# Sheet1.net
KiCad netlist of a schematic drawn in Altium Designer
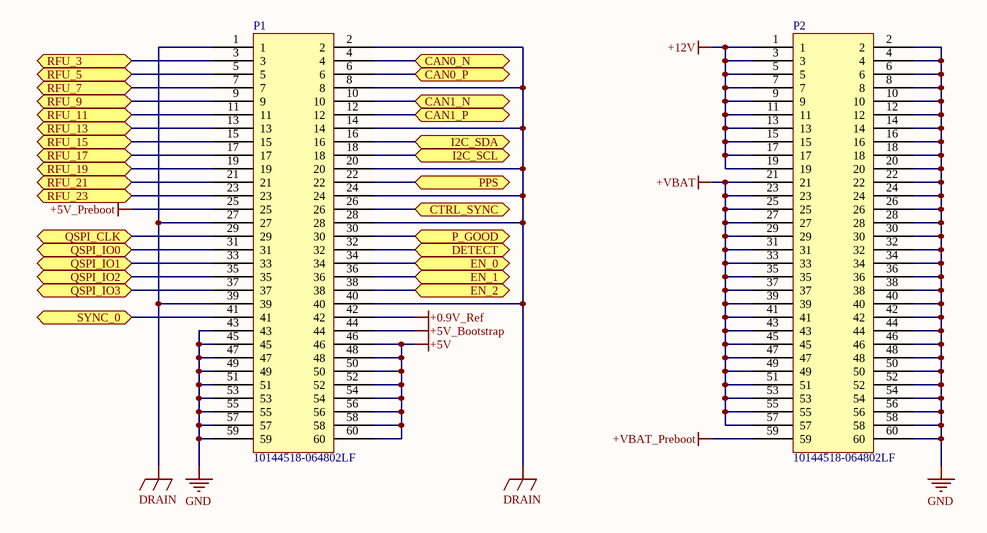
[diagram p0: Sheet1.SchDoc]

(export (version "E")
  (design (tool "Eeschema 10.0.6"))
  (components
    (comp (ref "P1")
      (value "10144518-064802LF")
      (footprint "10144518-064802LF")
      (libsource (lib "ModularPayload") (part "10144518-064802LF"))
    )
    (comp (ref "P2")
      (value "10144518-064802LF")
      (footprint "10144518-064802LF")
      (libsource (lib "ModularPayload") (part "10144518-064802LF"))
    )
  )
  (nets
    (net (code "1") (name "+0.9V_Ref") (class "Default")
      (node (ref "P1") (pin "42") (pinfunction "42_42") (pintype "passive"))
    )
    (net (code "2") (name "+5V") (class "Default")
      (node (ref "P1") (pin "46") (pinfunction "46_46") (pintype "passive"))
      (node (ref "P1") (pin "48") (pinfunction "48_48") (pintype "passive"))
      (node (ref "P1") (pin "50") (pinfunction "50_50") (pintype "passive"))
      (node (ref "P1") (pin "52") (pinfunction "52_52") (pintype "passive"))
      (node (ref "P1") (pin "54") (pinfunction "54_54") (pintype "passive"))
      (node (ref "P1") (pin "56") (pinfunction "56_56") (pintype "passive"))
      (node (ref "P1") (pin "58") (pinfunction "58_58") (pintype "passive"))
      (node (ref "P1") (pin "60") (pinfunction "60_60") (pintype "passive"))
    )
    (net (code "3") (name "+5V_Bootstrap") (class "Default")
      (node (ref "P1") (pin "44") (pinfunction "44_44") (pintype "passive"))
    )
    (net (code "4") (name "+5V_Preboot") (class "Default")
      (node (ref "P1") (pin "25") (pinfunction "25_25") (pintype "passive"))
    )
    (net (code "5") (name "+12V") (class "Default")
      (node (ref "P2") (pin "1") (pinfunction "1_1") (pintype "passive"))
      (node (ref "P2") (pin "11") (pinfunction "11_11") (pintype "passive"))
      (node (ref "P2") (pin "13") (pinfunction "13_13") (pintype "passive"))
      (node (ref "P2") (pin "15") (pinfunction "15_15") (pintype "passive"))
      (node (ref "P2") (pin "17") (pinfunction "17_17") (pintype "passive"))
      (node (ref "P2") (pin "19") (pinfunction "19_19") (pintype "passive"))
      (node (ref "P2") (pin "3") (pinfunction "3_3") (pintype "passive"))
      (node (ref "P2") (pin "5") (pinfunction "5_5") (pintype "passive"))
      (node (ref "P2") (pin "7") (pinfunction "7_7") (pintype "passive"))
      (node (ref "P2") (pin "9") (pinfunction "9_9") (pintype "passive"))
    )
    (net (code "6") (name "+VBAT") (class "Default")
      (node (ref "P2") (pin "21") (pinfunction "21_21") (pintype "passive"))
      (node (ref "P2") (pin "23") (pinfunction "23_23") (pintype "passive"))
      (node (ref "P2") (pin "25") (pinfunction "25_25") (pintype "passive"))
      (node (ref "P2") (pin "27") (pinfunction "27_27") (pintype "passive"))
      (node (ref "P2") (pin "29") (pinfunction "29_29") (pintype "passive"))
      (node (ref "P2") (pin "31") (pinfunction "31_31") (pintype "passive"))
      (node (ref "P2") (pin "33") (pinfunction "33_33") (pintype "passive"))
      (node (ref "P2") (pin "35") (pinfunction "35_35") (pintype "passive"))
      (node (ref "P2") (pin "37") (pinfunction "37_37") (pintype "passive"))
      (node (ref "P2") (pin "39") (pinfunction "39_39") (pintype "passive"))
      (node (ref "P2") (pin "41") (pinfunction "41_41") (pintype "passive"))
      (node (ref "P2") (pin "43") (pinfunction "43_43") (pintype "passive"))
      (node (ref "P2") (pin "45") (pinfunction "45_45") (pintype "passive"))
      (node (ref "P2") (pin "47") (pinfunction "47_47") (pintype "passive"))
      (node (ref "P2") (pin "49") (pinfunction "49_49") (pintype "passive"))
      (node (ref "P2") (pin "51") (pinfunction "51_51") (pintype "passive"))
      (node (ref "P2") (pin "53") (pinfunction "53_53") (pintype "passive"))
      (node (ref "P2") (pin "55") (pinfunction "55_55") (pintype "passive"))
      (node (ref "P2") (pin "57") (pinfunction "57_57") (pintype "passive"))
    )
    (net (code "7") (name "+VBAT_Preboot") (class "Default")
      (node (ref "P2") (pin "59") (pinfunction "59_59") (pintype "passive"))
    )
    (net (code "8") (name "/CAN0_N") (class "Default")
      (node (ref "P1") (pin "4") (pinfunction "4_4") (pintype "passive"))
    )
    (net (code "9") (name "/CAN0_P") (class "Default")
      (node (ref "P1") (pin "6") (pinfunction "6_6") (pintype "passive"))
    )
    (net (code "10") (name "/CAN1_N") (class "Default")
      (node (ref "P1") (pin "10") (pinfunction "10_10") (pintype "passive"))
    )
    (net (code "11") (name "/CAN1_P") (class "Default")
      (node (ref "P1") (pin "12") (pinfunction "12_12") (pintype "passive"))
    )
    (net (code "12") (name "/CTRL_SYNC") (class "Default")
      (node (ref "P1") (pin "26") (pinfunction "26_26") (pintype "passive"))
    )
    (net (code "13") (name "/DETECT") (class "Default")
      (node (ref "P1") (pin "32") (pinfunction "32_32") (pintype "passive"))
    )
    (net (code "14") (name "/EN_0") (class "Default")
      (node (ref "P1") (pin "34") (pinfunction "34_34") (pintype "passive"))
    )
    (net (code "15") (name "/EN_1") (class "Default")
      (node (ref "P1") (pin "36") (pinfunction "36_36") (pintype "passive"))
    )
    (net (code "16") (name "/EN_2") (class "Default")
      (node (ref "P1") (pin "38") (pinfunction "38_38") (pintype "passive"))
    )
    (net (code "17") (name "/I2C_SCL") (class "Default")
      (node (ref "P1") (pin "18") (pinfunction "18_18") (pintype "passive"))
    )
    (net (code "18") (name "/I2C_SDA") (class "Default")
      (node (ref "P1") (pin "16") (pinfunction "16_16") (pintype "passive"))
    )
    (net (code "19") (name "/PPS") (class "Default")
      (node (ref "P1") (pin "22") (pinfunction "22_22") (pintype "passive"))
    )
    (net (code "20") (name "/P_GOOD") (class "Default")
      (node (ref "P1") (pin "30") (pinfunction "30_30") (pintype "passive"))
    )
    (net (code "21") (name "/QSPI_CLK") (class "Default")
      (node (ref "P1") (pin "29") (pinfunction "29_29") (pintype "passive"))
    )
    (net (code "22") (name "/QSPI_IO0") (class "Default")
      (node (ref "P1") (pin "31") (pinfunction "31_31") (pintype "passive"))
    )
    (net (code "23") (name "/QSPI_IO1") (class "Default")
      (node (ref "P1") (pin "33") (pinfunction "33_33") (pintype "passive"))
    )
    (net (code "24") (name "/QSPI_IO2") (class "Default")
      (node (ref "P1") (pin "35") (pinfunction "35_35") (pintype "passive"))
    )
    (net (code "25") (name "/QSPI_IO3") (class "Default")
      (node (ref "P1") (pin "37") (pinfunction "37_37") (pintype "passive"))
    )
    (net (code "26") (name "/RFU_3") (class "Default")
      (node (ref "P1") (pin "3") (pinfunction "3_3") (pintype "passive"))
    )
    (net (code "27") (name "/RFU_5") (class "Default")
      (node (ref "P1") (pin "5") (pinfunction "5_5") (pintype "passive"))
    )
    (net (code "28") (name "/RFU_7") (class "Default")
      (node (ref "P1") (pin "7") (pinfunction "7_7") (pintype "passive"))
    )
    (net (code "29") (name "/RFU_9") (class "Default")
      (node (ref "P1") (pin "9") (pinfunction "9_9") (pintype "passive"))
    )
    (net (code "30") (name "/RFU_11") (class "Default")
      (node (ref "P1") (pin "11") (pinfunction "11_11") (pintype "passive"))
    )
    (net (code "31") (name "/RFU_13") (class "Default")
      (node (ref "P1") (pin "13") (pinfunction "13_13") (pintype "passive"))
    )
    (net (code "32") (name "/RFU_15") (class "Default")
      (node (ref "P1") (pin "15") (pinfunction "15_15") (pintype "passive"))
    )
    (net (code "33") (name "/RFU_17") (class "Default")
      (node (ref "P1") (pin "17") (pinfunction "17_17") (pintype "passive"))
    )
    (net (code "34") (name "/RFU_19") (class "Default")
      (node (ref "P1") (pin "19") (pinfunction "19_19") (pintype "passive"))
    )
    (net (code "35") (name "/RFU_21") (class "Default")
      (node (ref "P1") (pin "21") (pinfunction "21_21") (pintype "passive"))
    )
    (net (code "36") (name "/RFU_23") (class "Default")
      (node (ref "P1") (pin "23") (pinfunction "23_23") (pintype "passive"))
    )
    (net (code "37") (name "/SYNC_0") (class "Default")
      (node (ref "P1") (pin "41") (pinfunction "41_41") (pintype "passive"))
    )
    (net (code "38") (name "DRAIN") (class "Default")
      (node (ref "P1") (pin "1") (pinfunction "1_1") (pintype "passive"))
      (node (ref "P1") (pin "14") (pinfunction "14_14") (pintype "passive"))
      (node (ref "P1") (pin "2") (pinfunction "2_2") (pintype "passive"))
      (node (ref "P1") (pin "20") (pinfunction "20_20") (pintype "passive"))
      (node (ref "P1") (pin "24") (pinfunction "24_24") (pintype "passive"))
      (node (ref "P1") (pin "27") (pinfunction "27_27") (pintype "passive"))
      (node (ref "P1") (pin "28") (pinfunction "28_28") (pintype "passive"))
      (node (ref "P1") (pin "39") (pinfunction "39_39") (pintype "passive"))
      (node (ref "P1") (pin "40") (pinfunction "40_40") (pintype "passive"))
      (node (ref "P1") (pin "8") (pinfunction "8_8") (pintype "passive"))
    )
    (net (code "39") (name "GND") (class "Default")
      (node (ref "P1") (pin "43") (pinfunction "43_43") (pintype "passive"))
      (node (ref "P1") (pin "45") (pinfunction "45_45") (pintype "passive"))
      (node (ref "P1") (pin "47") (pinfunction "47_47") (pintype "passive"))
      (node (ref "P1") (pin "49") (pinfunction "49_49") (pintype "passive"))
      (node (ref "P1") (pin "51") (pinfunction "51_51") (pintype "passive"))
      (node (ref "P1") (pin "53") (pinfunction "53_53") (pintype "passive"))
      (node (ref "P1") (pin "55") (pinfunction "55_55") (pintype "passive"))
      (node (ref "P1") (pin "57") (pinfunction "57_57") (pintype "passive"))
      (node (ref "P1") (pin "59") (pinfunction "59_59") (pintype "passive"))
      (node (ref "P2") (pin "10") (pinfunction "10_10") (pintype "passive"))
      (node (ref "P2") (pin "12") (pinfunction "12_12") (pintype "passive"))
      (node (ref "P2") (pin "14") (pinfunction "14_14") (pintype "passive"))
      (node (ref "P2") (pin "16") (pinfunction "16_16") (pintype "passive"))
      (node (ref "P2") (pin "18") (pinfunction "18_18") (pintype "passive"))
      (node (ref "P2") (pin "2") (pinfunction "2_2") (pintype "passive"))
      (node (ref "P2") (pin "20") (pinfunction "20_20") (pintype "passive"))
      (node (ref "P2") (pin "22") (pinfunction "22_22") (pintype "passive"))
      (node (ref "P2") (pin "24") (pinfunction "24_24") (pintype "passive"))
      (node (ref "P2") (pin "26") (pinfunction "26_26") (pintype "passive"))
      (node (ref "P2") (pin "28") (pinfunction "28_28") (pintype "passive"))
      (node (ref "P2") (pin "30") (pinfunction "30_30") (pintype "passive"))
      (node (ref "P2") (pin "32") (pinfunction "32_32") (pintype "passive"))
      (node (ref "P2") (pin "34") (pinfunction "34_34") (pintype "passive"))
      (node (ref "P2") (pin "36") (pinfunction "36_36") (pintype "passive"))
      (node (ref "P2") (pin "38") (pinfunction "38_38") (pintype "passive"))
      (node (ref "P2") (pin "4") (pinfunction "4_4") (pintype "passive"))
      (node (ref "P2") (pin "40") (pinfunction "40_40") (pintype "passive"))
      (node (ref "P2") (pin "42") (pinfunction "42_42") (pintype "passive"))
      (node (ref "P2") (pin "44") (pinfunction "44_44") (pintype "passive"))
      (node (ref "P2") (pin "46") (pinfunction "46_46") (pintype "passive"))
      (node (ref "P2") (pin "48") (pinfunction "48_48") (pintype "passive"))
      (node (ref "P2") (pin "50") (pinfunction "50_50") (pintype "passive"))
      (node (ref "P2") (pin "52") (pinfunction "52_52") (pintype "passive"))
      (node (ref "P2") (pin "54") (pinfunction "54_54") (pintype "passive"))
      (node (ref "P2") (pin "56") (pinfunction "56_56") (pintype "passive"))
      (node (ref "P2") (pin "58") (pinfunction "58_58") (pintype "passive"))
      (node (ref "P2") (pin "6") (pinfunction "6_6") (pintype "passive"))
      (node (ref "P2") (pin "60") (pinfunction "60_60") (pintype "passive"))
      (node (ref "P2") (pin "8") (pinfunction "8_8") (pintype "passive"))
    )
  )
)
